# c3-card.net
KiCad netlist of a schematic drawn in EAGLE
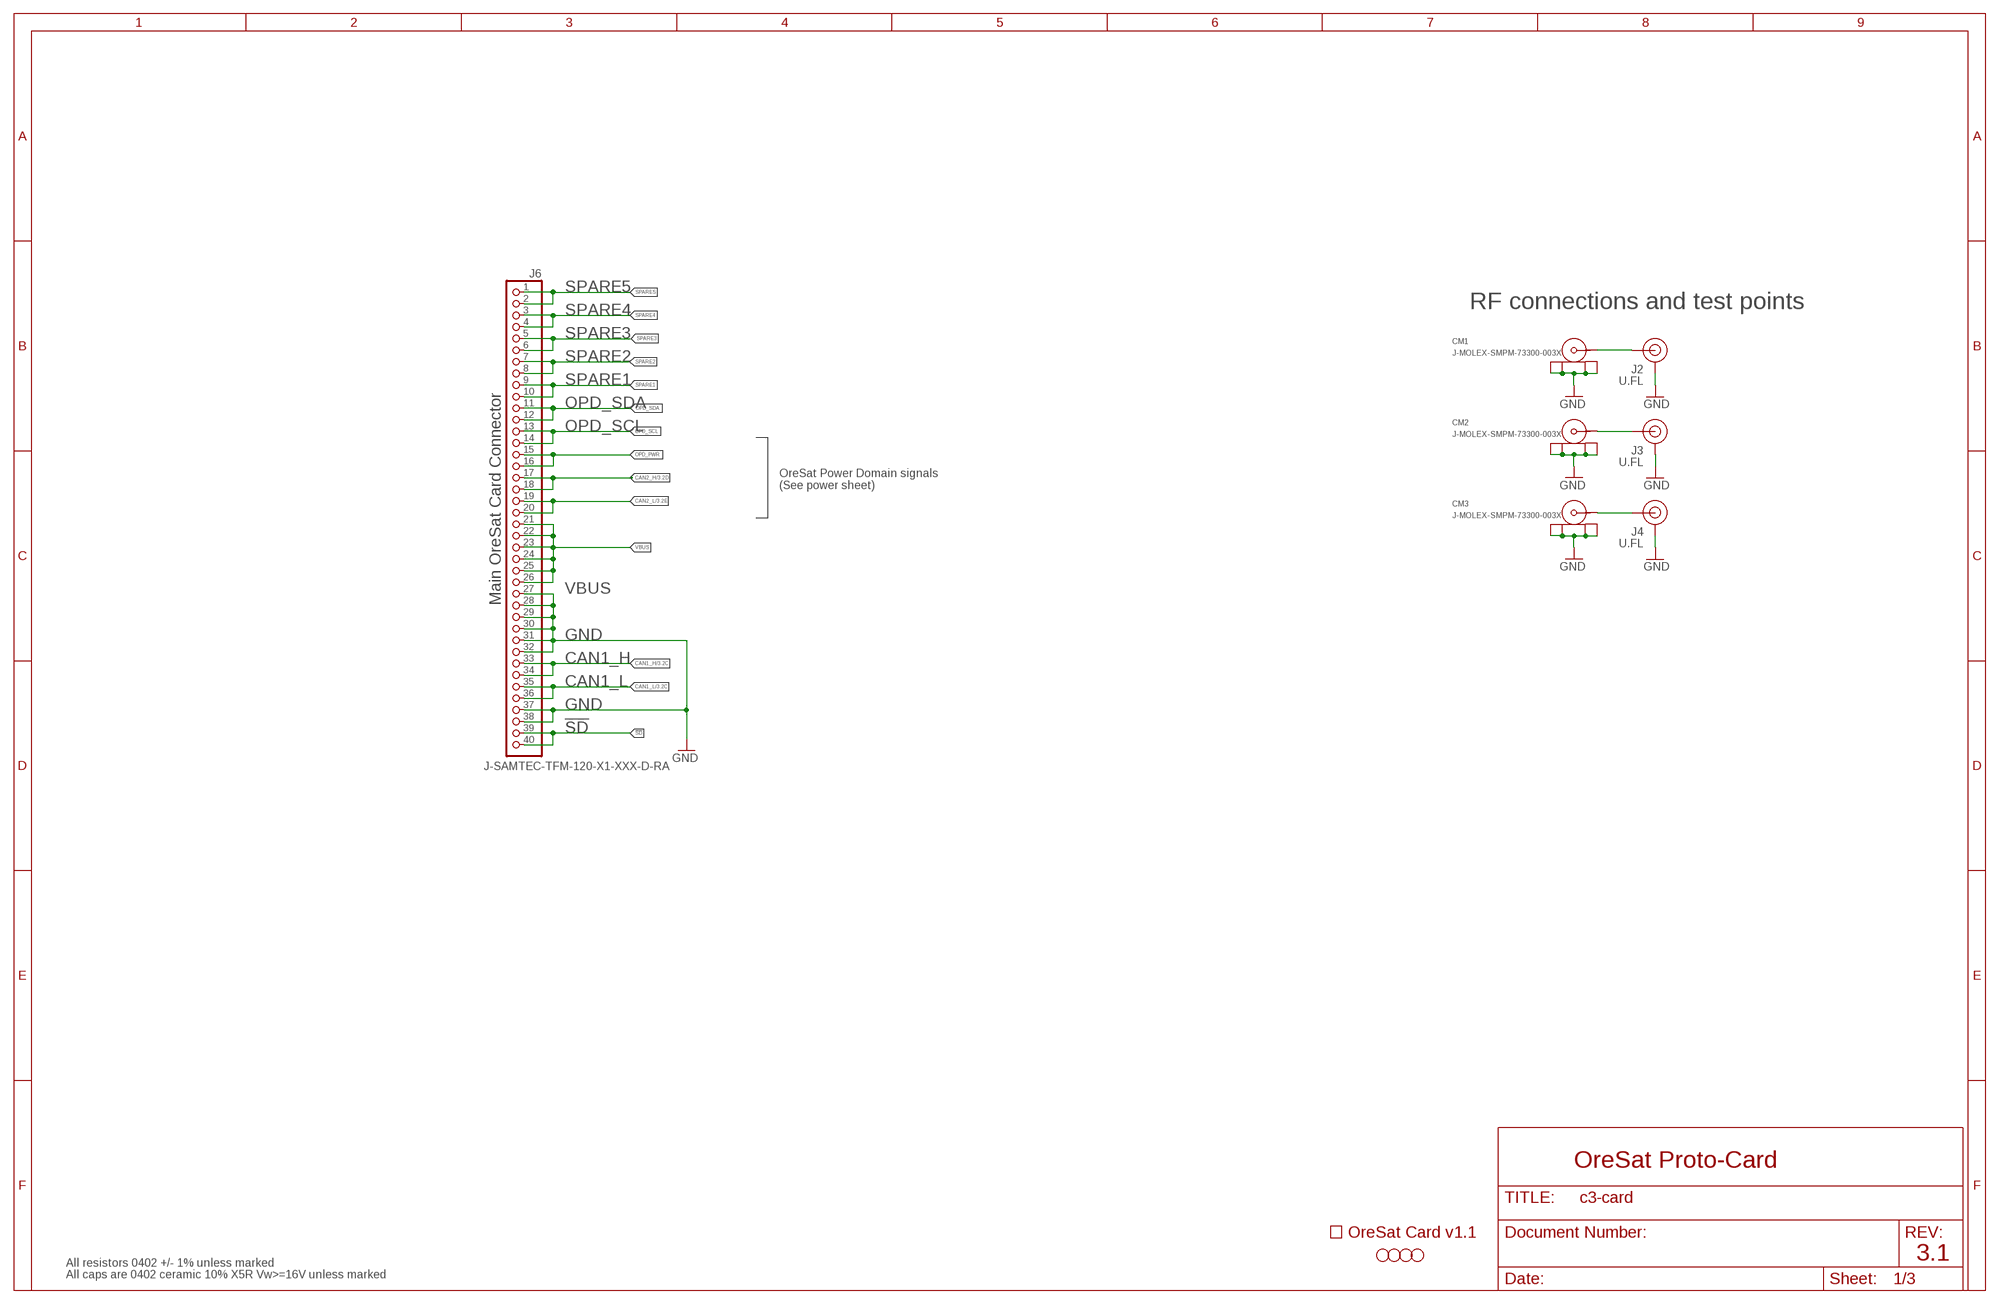
[diagram p0: schematic, sheet 1]
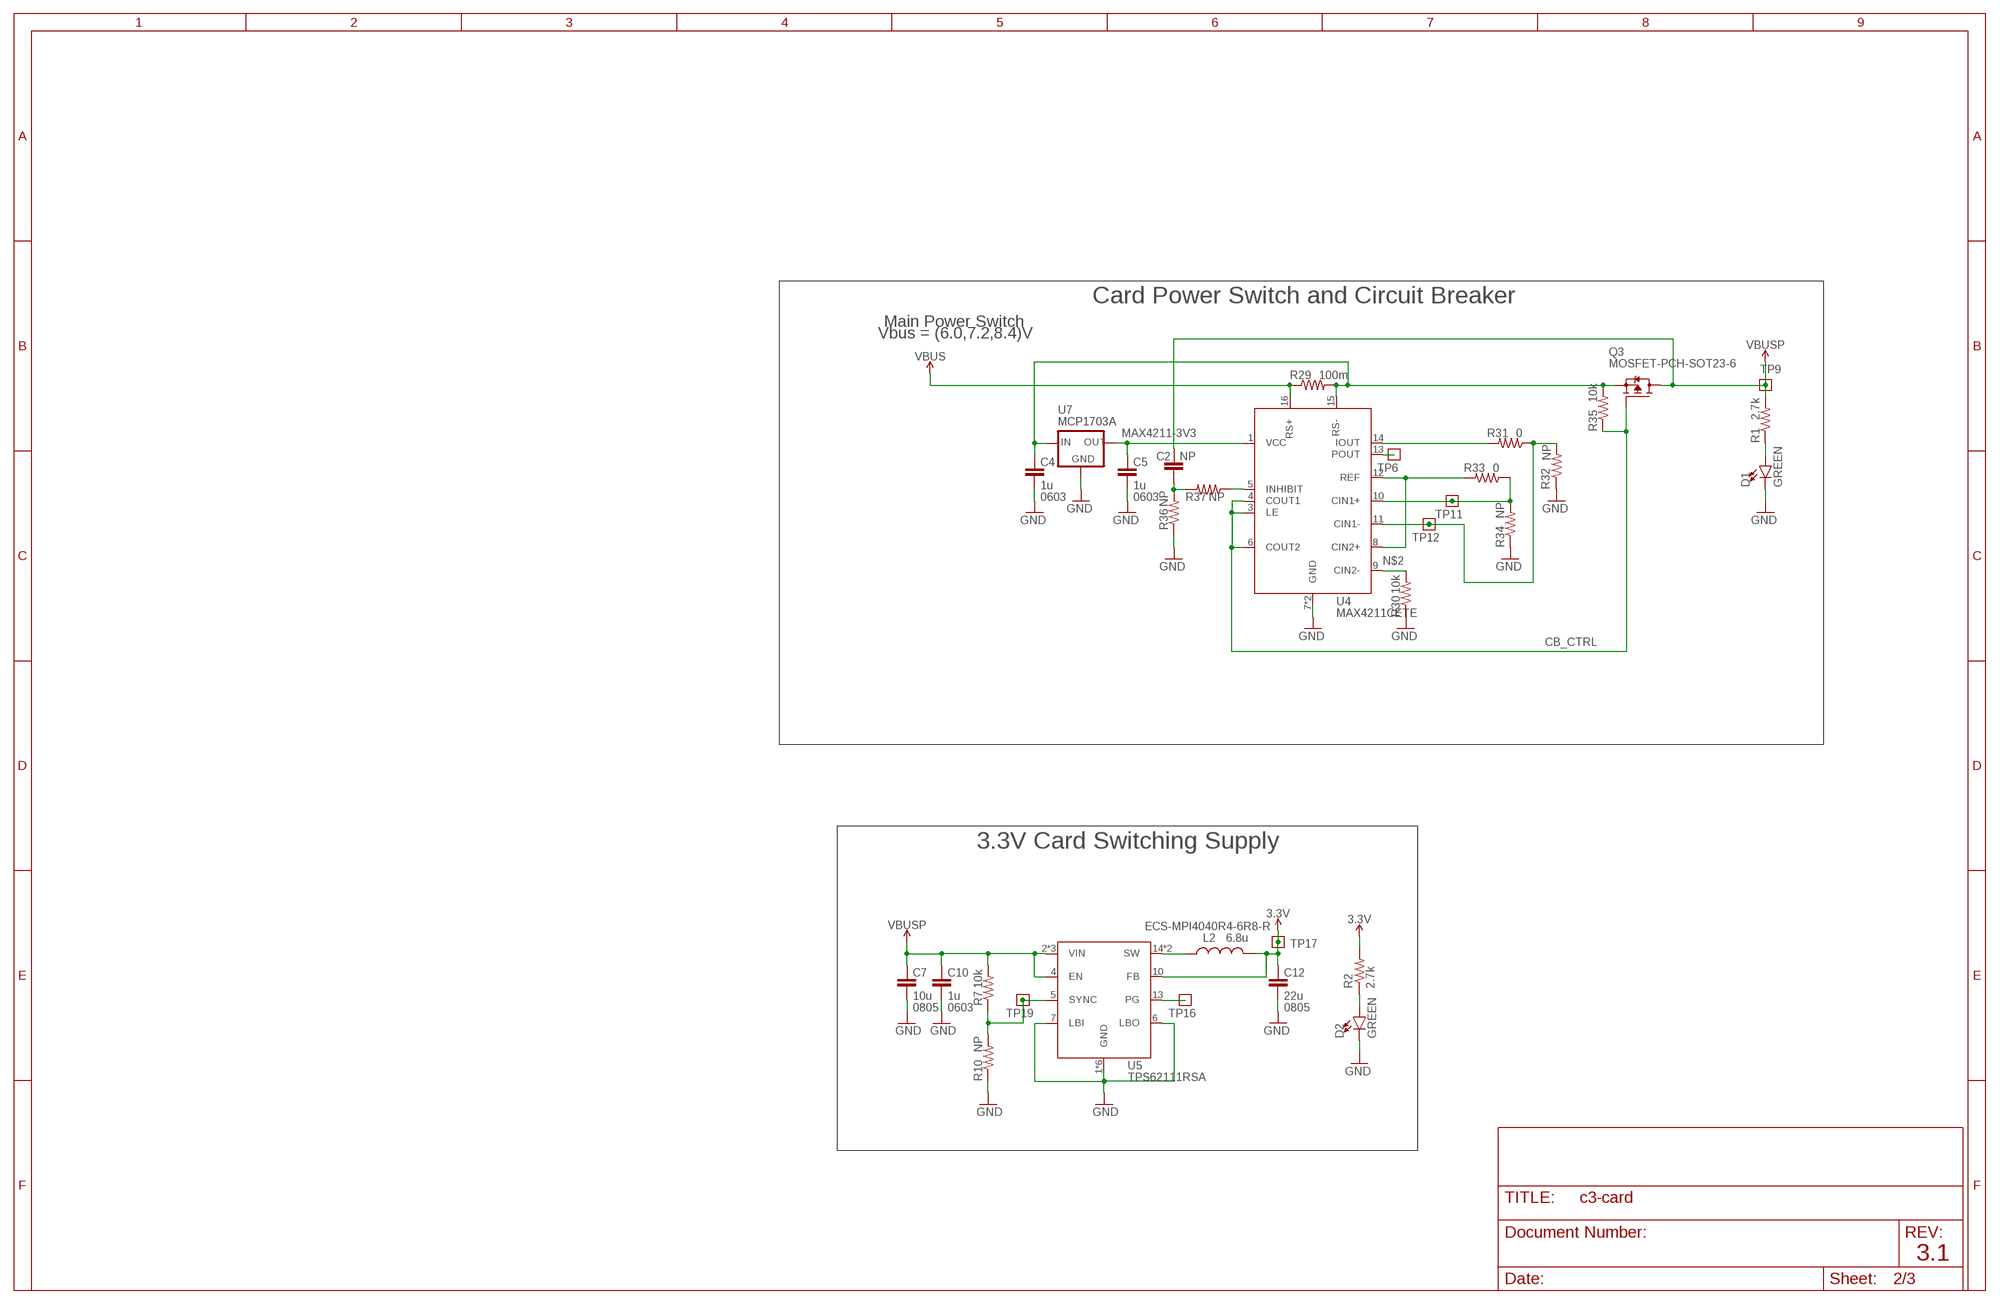
[diagram p1: schematic, sheet 2]
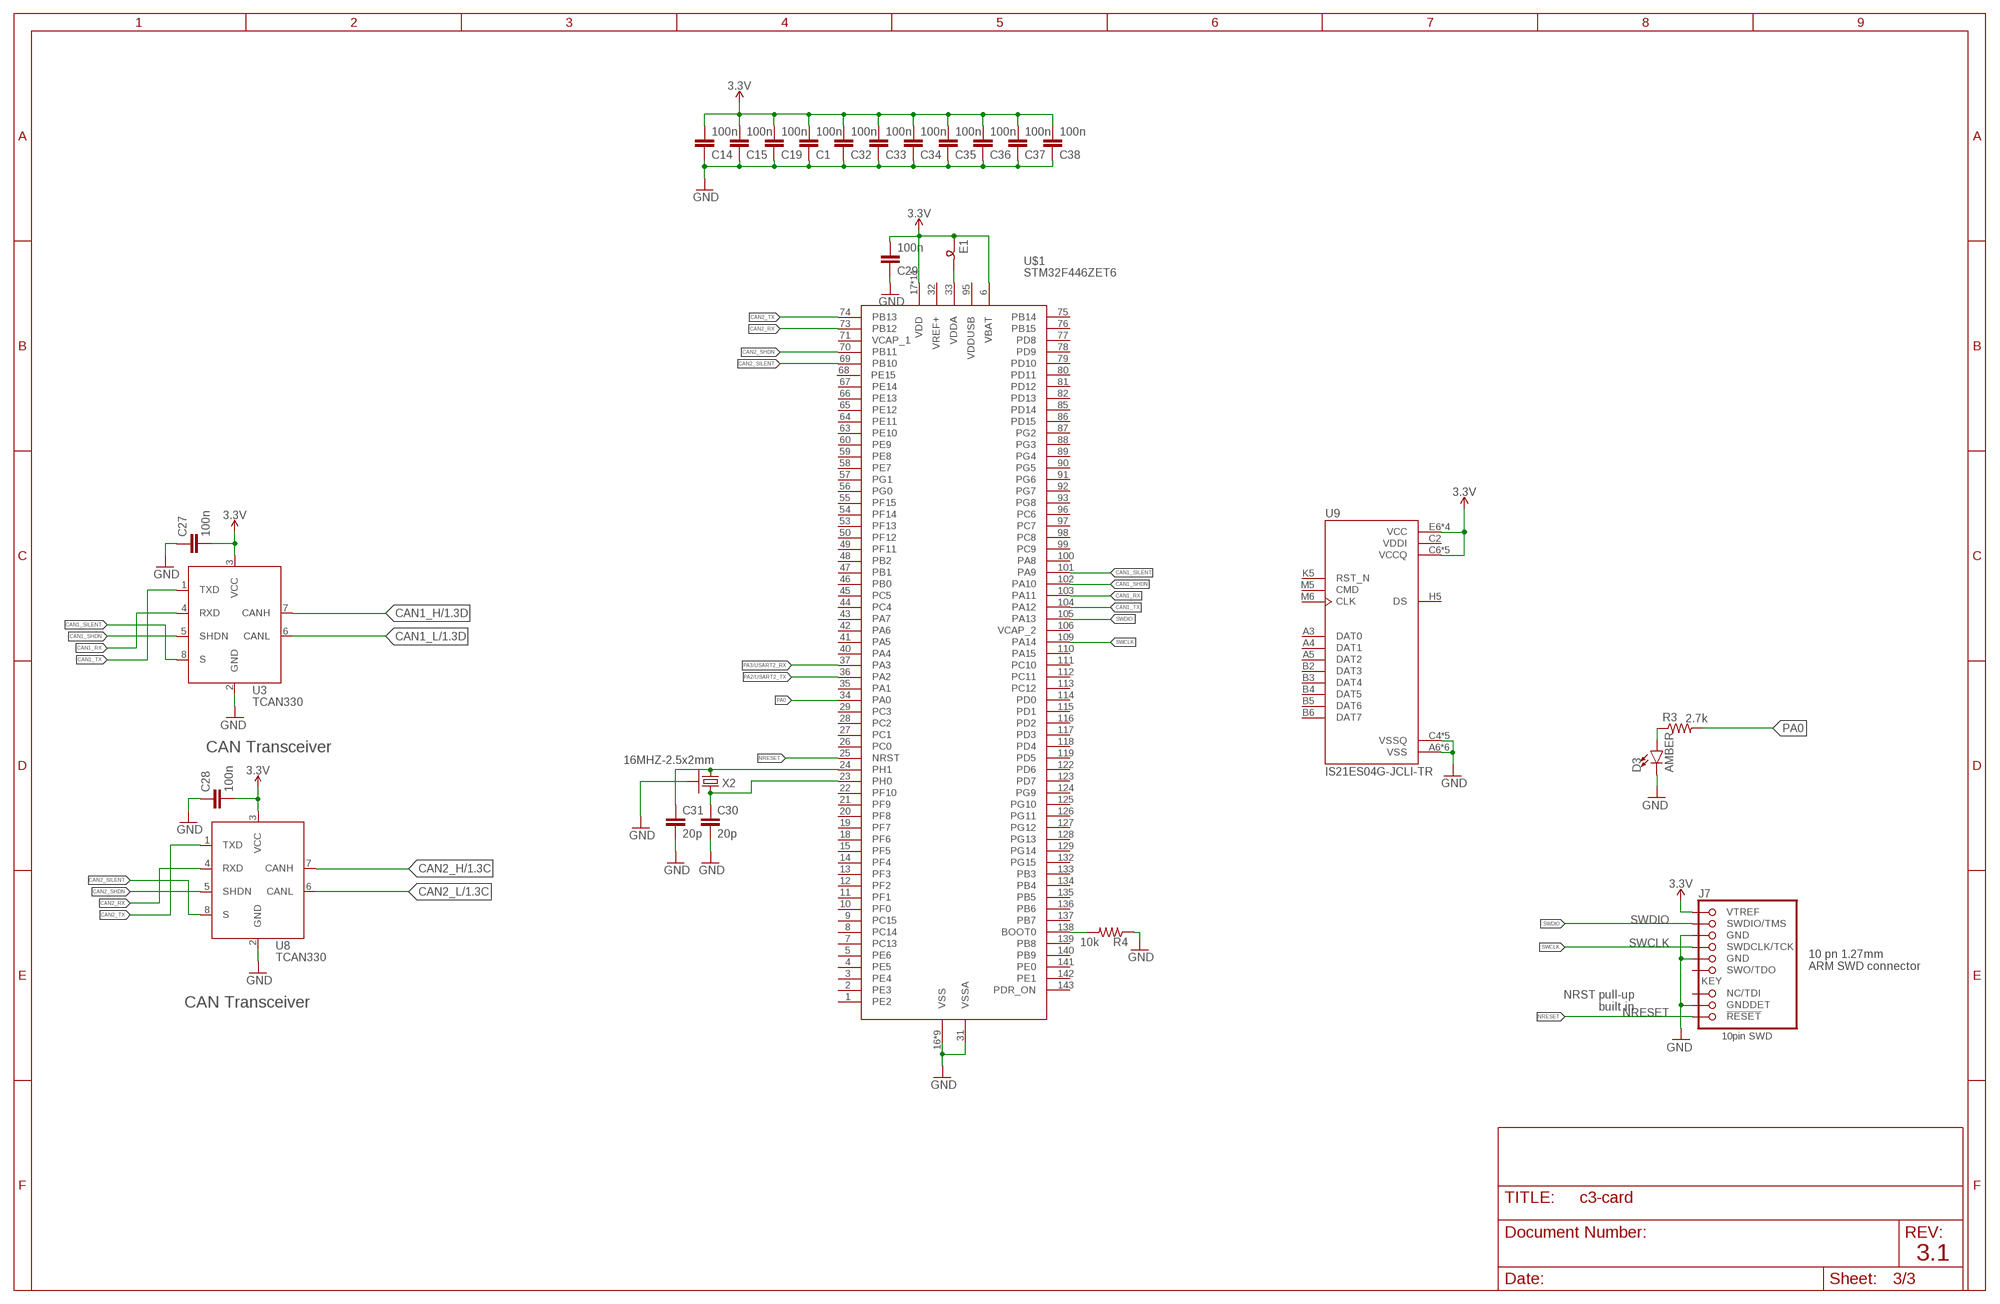
[diagram p2: schematic, sheet 3]

(export (version "E")
  (design (tool "Eeschema 10.0.6"))
  (components
    (comp (ref "C2")
      (value "NP")
      (footprint "eagle-import:.0402-B-NOSILK")
      (fields (field (name "MFR") "Samsung") (field (name "MPN") "CL05B104KO5NNNC"))
      (libsource (lib "eagle-import") (part "rcl_custom_C-EU0402-B-NOSILK"))
    )
    (comp (ref "C4")
      (value "1u")
      (footprint "eagle-import:.0603-B-NOSILK")
      (fields (field (name "MFR") "Samsung") (field (name "MPN") "CL05B104KO5NNNC"))
      (libsource (lib "eagle-import") (part "C-EU0603-B-NOSILK"))
    )
    (comp (ref "C5")
      (value "1u")
      (footprint "eagle-import:.0603-B-NOSILK")
      (fields (field (name "MFR") "Samsung") (field (name "MPN") "CL05B104KO5NNNC"))
      (libsource (lib "eagle-import") (part "C-EU0603-B-NOSILK"))
    )
    (comp (ref "C7")
      (value "10u")
      (footprint "eagle-import:.0805-B-NOSILK")
      (libsource (lib "eagle-import") (part "C-EU0805-B-NOSILK"))
    )
    (comp (ref "C10")
      (value "1u")
      (footprint "eagle-import:.0603-B-NOSILK")
      (fields (field (name "MFR") "Samsung") (field (name "MPN") "CL05B104KO5NNNC"))
      (libsource (lib "eagle-import") (part "C-EU0603-B-NOSILK"))
    )
    (comp (ref "C12")
      (value "22u")
      (footprint "eagle-import:.0805-B-NOSILK")
      (libsource (lib "eagle-import") (part "C-EU0805-B-NOSILK"))
    )
    (comp (ref "D1")
      (value "GREEN")
      (footprint "eagle-import:LED-0603")
      (libsource (lib "eagle-import") (part "LED-GREEN0603"))
    )
    (comp (ref "D2")
      (value "GREEN")
      (footprint "eagle-import:LED-0603")
      (libsource (lib "eagle-import") (part "LED-GREEN0603"))
    )
    (comp (ref "L2")
      (value "6.8u")
      (footprint "eagle-import:ECS-MPI4040")
      (fields (field (name "MFR") "ECS") (field (name "MPN") "ECS-MPI4040R4-6R8-R"))
      (libsource (lib "eagle-import") (part "L-ECS-MPI4040"))
    )
    (comp (ref "Q3")
      (value "MOSFET-PCH-SOT23-6")
      (footprint "eagle-import:SOT23-6")
      (fields (field (name "MFR") "Diodes Inc") (field (name "MPN") "DMP3050LVT-7"))
      (libsource (lib "eagle-import") (part "MOSFET-PCH-SOT23-6"))
    )
    (comp (ref "R1")
      (value "2.7k")
      (footprint "eagle-import:.0402-B-NOSILK")
      (fields (field (name "MFR") "Samsung") (field (name "MPN") "RC1005F6653CS"))
      (libsource (lib "eagle-import") (part "R-US_0402-B-NOSILK"))
    )
    (comp (ref "R2")
      (value "2.7k")
      (footprint "eagle-import:.0402-B-NOSILK")
      (fields (field (name "MFR") "Samsung") (field (name "MPN") "RC1005F6653CS"))
      (libsource (lib "eagle-import") (part "R-US_0402-B-NOSILK"))
    )
    (comp (ref "R7")
      (value "10k")
      (footprint "eagle-import:.0402-B-NOSILK")
      (fields (field (name "MFR") "Samsung") (field (name "MPN") "RC1005F6653CS"))
      (libsource (lib "eagle-import") (part "R-US_0402-B-NOSILK"))
    )
    (comp (ref "R10")
      (value "NP")
      (footprint "eagle-import:.0402-B-NOSILK")
      (fields (field (name "MFR") "Samsung") (field (name "MPN") "RC1005F6653CS"))
      (libsource (lib "eagle-import") (part "R-US_0402-B-NOSILK"))
    )
    (comp (ref "R29")
      (value "100m")
      (footprint "eagle-import:R1206")
      (libsource (lib "eagle-import") (part "R-US_R1206"))
    )
    (comp (ref "R30")
      (value "10k")
      (footprint "eagle-import:.0402-B-NOSILK")
      (fields (field (name "MFR") "Samsung") (field (name "MPN") "RC1005F6653CS"))
      (libsource (lib "eagle-import") (part "R-US_0402-B-NOSILK"))
    )
    (comp (ref "R31")
      (value "0")
      (footprint "eagle-import:.0402-B-NOSILK")
      (fields (field (name "MFR") "Samsung") (field (name "MPN") "RC1005F6653CS"))
      (libsource (lib "eagle-import") (part "R-US_0402-B-NOSILK"))
    )
    (comp (ref "R32")
      (value "NP")
      (footprint "eagle-import:.0402-B-NOSILK")
      (fields (field (name "MFR") "Samsung") (field (name "MPN") "RC1005F6653CS"))
      (libsource (lib "eagle-import") (part "R-US_0402-B-NOSILK"))
    )
    (comp (ref "R33")
      (value "0")
      (footprint "eagle-import:.0402-B-NOSILK")
      (fields (field (name "MFR") "Samsung") (field (name "MPN") "RC1005F6653CS"))
      (libsource (lib "eagle-import") (part "R-US_0402-B-NOSILK"))
    )
    (comp (ref "R34")
      (value "NP")
      (footprint "eagle-import:.0402-B-NOSILK")
      (fields (field (name "MFR") "Samsung") (field (name "MPN") "RC1005F6653CS"))
      (libsource (lib "eagle-import") (part "R-US_0402-B-NOSILK"))
    )
    (comp (ref "R35")
      (value "10k")
      (footprint "eagle-import:.0402-B-NOSILK")
      (fields (field (name "MFR") "Samsung") (field (name "MPN") "RC1005F6653CS"))
      (libsource (lib "eagle-import") (part "R-US_0402-B-NOSILK"))
    )
    (comp (ref "R36")
      (value "NP")
      (footprint "eagle-import:.0402-B-NOSILK")
      (fields (field (name "MFR") "Samsung") (field (name "MPN") "RC1005F6653CS"))
      (libsource (lib "eagle-import") (part "R-US_0402-B-NOSILK"))
    )
    (comp (ref "R37")
      (value "NP")
      (footprint "eagle-import:.0402-B-NOSILK")
      (fields (field (name "MFR") "Samsung") (field (name "MPN") "RC1005F6653CS"))
      (libsource (lib "eagle-import") (part "R-US_0402-B-NOSILK"))
    )
    (comp (ref "TP6")
      (value "TEST-POINT")
      (footprint "eagle-import:2MM-TEST-POINT")
      (libsource (lib "eagle-import") (part "TEST-POINT"))
    )
    (comp (ref "TP9")
      (value "TEST-POINT")
      (footprint "eagle-import:2MM-TEST-POINT")
      (libsource (lib "eagle-import") (part "TEST-POINT"))
    )
    (comp (ref "TP11")
      (value "TEST-POINT")
      (footprint "eagle-import:2MM-TEST-POINT")
      (libsource (lib "eagle-import") (part "TEST-POINT"))
    )
    (comp (ref "TP12")
      (value "TEST-POINT")
      (footprint "eagle-import:2MM-TEST-POINT")
      (libsource (lib "eagle-import") (part "TEST-POINT"))
    )
    (comp (ref "TP16")
      (value "TEST-POINT")
      (footprint "eagle-import:2MM-TEST-POINT")
      (libsource (lib "eagle-import") (part "TEST-POINT"))
    )
    (comp (ref "TP17")
      (value "TEST-POINT")
      (footprint "eagle-import:2MM-TEST-POINT")
      (libsource (lib "eagle-import") (part "TEST-POINT"))
    )
    (comp (ref "TP19")
      (value "TEST-POINT")
      (footprint "eagle-import:2MM-TEST-POINT")
      (libsource (lib "eagle-import") (part "TEST-POINT"))
    )
    (comp (ref "U4")
      (value "MAX4211CETE")
      (footprint "eagle-import:QFN65P400X400X80-17T210")
      (fields (field (name "MFR") "Maxim"))
      (libsource (lib "eagle-import") (part "MAX4211"))
    )
    (comp (ref "U5")
      (value "TPS62111RSA")
      (footprint "eagle-import:S-PVQFN-16")
      (fields (field (name "MFR") "TI"))
      (libsource (lib "eagle-import") (part "TPS6211X"))
    )
    (comp (ref "U7")
      (value "MCP1703A")
      (footprint "eagle-import:SOT23")
      (fields (field (name "MFR") "Microchip") (field (name "MPN") "MCP1703AT-3302E/CB"))
      (libsource (lib "eagle-import") (part "XC63FPM"))
    )
    (comp (ref "C1")
      (value "100n")
      (footprint "eagle-import:.0402-B-NOSILK")
      (fields (field (name "MFR") "Samsung") (field (name "MPN") "CL05B104KO5NNNC"))
      (libsource (lib "eagle-import") (part "rcl_custom_C-EU0402-B-NOSILK"))
    )
    (comp (ref "C14")
      (value "100n")
      (footprint "eagle-import:.0402-B-NOSILK")
      (fields (field (name "MFR") "Samsung") (field (name "MPN") "CL05B104KO5NNNC"))
      (libsource (lib "eagle-import") (part "rcl_custom_C-EU0402-B-NOSILK"))
    )
    (comp (ref "C15")
      (value "100n")
      (footprint "eagle-import:.0402-B-NOSILK")
      (fields (field (name "MFR") "Samsung") (field (name "MPN") "CL05B104KO5NNNC"))
      (libsource (lib "eagle-import") (part "rcl_custom_C-EU0402-B-NOSILK"))
    )
    (comp (ref "C19")
      (value "100n")
      (footprint "eagle-import:.0402-B-NOSILK")
      (fields (field (name "MFR") "Samsung") (field (name "MPN") "CL05B104KO5NNNC"))
      (libsource (lib "eagle-import") (part "rcl_custom_C-EU0402-B-NOSILK"))
    )
    (comp (ref "C27")
      (value "100n")
      (footprint "eagle-import:.0402-B-NOSILK")
      (fields (field (name "MFR") "Samsung") (field (name "MPN") "CL05B104KO5NNNC"))
      (libsource (lib "eagle-import") (part "rcl_custom_C-EU0402-B-NOSILK"))
    )
    (comp (ref "C28")
      (value "100n")
      (footprint "eagle-import:.0402-B-NOSILK")
      (fields (field (name "MFR") "Samsung") (field (name "MPN") "CL05B104KO5NNNC"))
      (libsource (lib "eagle-import") (part "rcl_custom_C-EU0402-B-NOSILK"))
    )
    (comp (ref "C29")
      (value "100n")
      (footprint "eagle-import:.0402-B-NOSILK")
      (fields (field (name "MFR") "Samsung") (field (name "MPN") "CL05B104KO5NNNC"))
      (libsource (lib "eagle-import") (part "rcl_custom_C-EU0402-B-NOSILK"))
    )
    (comp (ref "C30")
      (value "20p")
      (footprint "eagle-import:.0402-B-NOSILK")
      (fields (field (name "MFR") "Samsung") (field (name "MPN") "CL05C200JB51PNC"))
      (libsource (lib "eagle-import") (part "rcl_custom_C-EU0402-B-NOSILK"))
    )
    (comp (ref "C31")
      (value "20p")
      (footprint "eagle-import:.0402-B-NOSILK")
      (fields (field (name "MFR") "Samsung") (field (name "MPN") "CL05C200JB51PNC"))
      (libsource (lib "eagle-import") (part "rcl_custom_C-EU0402-B-NOSILK"))
    )
    (comp (ref "C32")
      (value "100n")
      (footprint "eagle-import:.0402-B-NOSILK")
      (fields (field (name "MFR") "Samsung") (field (name "MPN") "CL05B104KO5NNNC"))
      (libsource (lib "eagle-import") (part "rcl_custom_C-EU0402-B-NOSILK"))
    )
    (comp (ref "C33")
      (value "100n")
      (footprint "eagle-import:.0402-B-NOSILK")
      (fields (field (name "MFR") "Samsung") (field (name "MPN") "CL05B104KO5NNNC"))
      (libsource (lib "eagle-import") (part "rcl_custom_C-EU0402-B-NOSILK"))
    )
    (comp (ref "C34")
      (value "100n")
      (footprint "eagle-import:.0402-B-NOSILK")
      (fields (field (name "MFR") "Samsung") (field (name "MPN") "CL05B104KO5NNNC"))
      (libsource (lib "eagle-import") (part "rcl_custom_C-EU0402-B-NOSILK"))
    )
    (comp (ref "C35")
      (value "100n")
      (footprint "eagle-import:.0402-B-NOSILK")
      (fields (field (name "MFR") "Samsung") (field (name "MPN") "CL05B104KO5NNNC"))
      (libsource (lib "eagle-import") (part "rcl_custom_C-EU0402-B-NOSILK"))
    )
    (comp (ref "C36")
      (value "100n")
      (footprint "eagle-import:.0402-B-NOSILK")
      (fields (field (name "MFR") "Samsung") (field (name "MPN") "CL05B104KO5NNNC"))
      (libsource (lib "eagle-import") (part "rcl_custom_C-EU0402-B-NOSILK"))
    )
    (comp (ref "C37")
      (value "100n")
      (footprint "eagle-import:.0402-B-NOSILK")
      (fields (field (name "MFR") "Samsung") (field (name "MPN") "CL05B104KO5NNNC"))
      (libsource (lib "eagle-import") (part "rcl_custom_C-EU0402-B-NOSILK"))
    )
    (comp (ref "C38")
      (value "100n")
      (footprint "eagle-import:.0402-B-NOSILK")
      (fields (field (name "MFR") "Samsung") (field (name "MPN") "CL05B104KO5NNNC"))
      (libsource (lib "eagle-import") (part "rcl_custom_C-EU0402-B-NOSILK"))
    )
    (comp (ref "D3")
      (value "AMBER")
      (footprint "eagle-import:LED-0603")
      (libsource (lib "eagle-import") (part "LED-GREEN0603"))
    )
    (comp (ref "E1")
      (value "L-BEAD-0603-B")
      (footprint "eagle-import:.0603-B")
      (libsource (lib "eagle-import") (part "L-BEAD-0603-B"))
    )
    (comp (ref "J7")
      (value "FTSH-105-XX-X-DV-K")
      (footprint "eagle-import:CON10_2X5_DUK_FTSH")
      (fields (field (name "MFR") "Samtec") (field (name "MPN") "FTSH-105-01-F-DV-K"))
      (libsource (lib "eagle-import") (part "FTSH-105-XX-X-DV-K"))
    )
    (comp (ref "R3")
      (value "2.7k")
      (footprint "eagle-import:.0402-B-NOSILK")
      (fields (field (name "MFR") "Samsung") (field (name "MPN") "RC1005F6653CS"))
      (libsource (lib "eagle-import") (part "R-US_0402-B-NOSILK"))
    )
    (comp (ref "R4")
      (value "10k")
      (footprint "eagle-import:.0402-B-NOSILK")
      (fields (field (name "MFR") "Samsung") (field (name "MPN") "RC1005F6653CS"))
      (libsource (lib "eagle-import") (part "R-US_0402-B-NOSILK"))
    )
    (comp (ref "U$1")
      (value "STM32F446ZET6")
      (footprint "eagle-import:P-TQFP-144-19")
      (libsource (lib "eagle-import") (part "STM32F446ZET6"))
    )
    (comp (ref "U3")
      (value "TCAN330")
      (footprint "eagle-import:SOT23-8_TI-DCN")
      (fields (field (name "MFR") "Texas Instruments") (field (name "MPN") "TCAN330GDCNT"))
      (libsource (lib "eagle-import") (part "TCAN330"))
    )
    (comp (ref "U8")
      (value "TCAN330")
      (footprint "eagle-import:SOT23-8_TI-DCN")
      (fields (field (name "MFR") "Texas Instruments") (field (name "MPN") "TCAN330GDCNT"))
      (libsource (lib "eagle-import") (part "TCAN330"))
    )
    (comp (ref "U9")
      (value "IS21ES04G-JCLI-TR")
      (footprint "eagle-import:BGA153N50P14X14_1150X1300X100")
      (fields (field (name "MF") "ISSI, Integrated Silicon Solution Inc"))
      (libsource (lib "eagle-import") (part "IS21ES04G-JCLI-TR"))
    )
    (comp (ref "X2")
      (value "16MHZ-2.5x2mm")
      (footprint "eagle-import:CRYSTAL_2.5X2")
      (fields (field (name "MFR") "ECS Inc.") (field (name "MPN") "ECS-160-10-36Q-ES-TR"))
      (libsource (lib "eagle-import") (part "CRYSTAL-WITH-GND"))
    )
    (comp (ref "CM1")
      (value "J-MOLEX-SMPM-73300-003X")
      (footprint "eagle-import:J-MOLEX-SMPM-073300-003X")
      (fields (field (name "MFR") "Molex") (field (name "MPN") "73300-0020"))
      (libsource (lib "eagle-import") (part "J-MOLEX-SMPM-73300-003X"))
    )
    (comp (ref "CM2")
      (value "J-MOLEX-SMPM-73300-003X")
      (footprint "eagle-import:J-MOLEX-SMPM-073300-003X")
      (fields (field (name "MFR") "Molex") (field (name "MPN") "73300-0020"))
      (libsource (lib "eagle-import") (part "J-MOLEX-SMPM-73300-003X"))
    )
    (comp (ref "CM3")
      (value "J-MOLEX-SMPM-73300-003X")
      (footprint "eagle-import:J-MOLEX-SMPM-073300-003X")
      (fields (field (name "MFR") "Molex") (field (name "MPN") "73300-0020"))
      (libsource (lib "eagle-import") (part "J-MOLEX-SMPM-73300-003X"))
    )
    (comp (ref "H1")
      (value "STAND-OFFTIGHT")
      (footprint "eagle-import:STAND-OFF-TIGHT")
      (libsource (lib "eagle-import") (part "STAND-OFFTIGHT"))
    )
    (comp (ref "H2")
      (value "STAND-OFFTIGHT")
      (footprint "eagle-import:STAND-OFF-TIGHT")
      (libsource (lib "eagle-import") (part "STAND-OFFTIGHT"))
    )
    (comp (ref "H3")
      (value "STAND-OFFTIGHT")
      (footprint "eagle-import:STAND-OFF-TIGHT")
      (libsource (lib "eagle-import") (part "STAND-OFFTIGHT"))
    )
    (comp (ref "H4")
      (value "STAND-OFFTIGHT")
      (footprint "eagle-import:STAND-OFF-TIGHT")
      (libsource (lib "eagle-import") (part "STAND-OFFTIGHT"))
    )
    (comp (ref "J2")
      (value "U.FL")
      (footprint "eagle-import:U.FL")
      (libsource (lib "eagle-import") (part "U.FL2PIN"))
    )
    (comp (ref "J3")
      (value "U.FL")
      (footprint "eagle-import:U.FL")
      (libsource (lib "eagle-import") (part "U.FL2PIN"))
    )
    (comp (ref "J4")
      (value "U.FL")
      (footprint "eagle-import:U.FL")
      (libsource (lib "eagle-import") (part "U.FL2PIN"))
    )
    (comp (ref "J6")
      (value "J-SAMTEC-TFM-120-X1-XXX-D-RA")
      (footprint "eagle-import:J-SAMTEC-TFM-120-X1-XXX-D-RA")
      (fields (field (name "MFR") "Samtec") (field (name "MPN") "TFM-120-01-L-D-RA"))
      (libsource (lib "eagle-import") (part "J-SAMTEC-TFM-120-X1-XXX-D-RA"))
    )
    (comp (ref "U$2")
      (value "ORESAT-CARD-V1.1-3XRF")
      (footprint "eagle-import:ORESAT-CARD-V1.1-3XRF")
      (libsource (lib "eagle-import") (part "ORESAT-CARD-V1.1-3XRF"))
    )
  )
  (nets
    (net (code "1") (name "3.3V") (class "Default")
      (node (ref "C1") (pin "2") (pinfunction "2_2") (pintype "passive"))
      (node (ref "C12") (pin "1") (pinfunction "1_1") (pintype "passive"))
      (node (ref "C14") (pin "2") (pinfunction "2_2") (pintype "passive"))
      (node (ref "C15") (pin "2") (pinfunction "2_2") (pintype "passive"))
      (node (ref "C19") (pin "2") (pinfunction "2_2") (pintype "passive"))
      (node (ref "C27") (pin "2") (pinfunction "2_2") (pintype "passive"))
      (node (ref "C28") (pin "2") (pinfunction "2_2") (pintype "passive"))
      (node (ref "C29") (pin "2") (pinfunction "2_2") (pintype "passive"))
      (node (ref "C32") (pin "2") (pinfunction "2_2") (pintype "passive"))
      (node (ref "C33") (pin "2") (pinfunction "2_2") (pintype "passive"))
      (node (ref "C34") (pin "2") (pinfunction "2_2") (pintype "passive"))
      (node (ref "C35") (pin "2") (pinfunction "2_2") (pintype "passive"))
      (node (ref "C36") (pin "2") (pinfunction "2_2") (pintype "passive"))
      (node (ref "C37") (pin "2") (pinfunction "2_2") (pintype "passive"))
      (node (ref "C38") (pin "2") (pinfunction "2_2") (pintype "passive"))
      (node (ref "E1") (pin "1") (pinfunction "1_1") (pintype "passive"))
      (node (ref "J7") (pin "1") (pinfunction "VTREF_1") (pintype "passive"))
      (node (ref "L2") (pin "2") (pinfunction "2_2") (pintype "passive"))
      (node (ref "R2") (pin "2") (pinfunction "2_2") (pintype "passive"))
      (node (ref "TP17") (pin "1") (pinfunction "1_1") (pintype "passive"))
      (node (ref "U$1") (pin "108") (pinfunction "VDD_108") (pintype "bidirectional"))
      (node (ref "U$1") (pin "121") (pinfunction "VDD_121") (pintype "bidirectional"))
      (node (ref "U$1") (pin "131") (pinfunction "VDD_131") (pintype "bidirectional"))
      (node (ref "U$1") (pin "144") (pinfunction "VDD_144") (pintype "bidirectional"))
      (node (ref "U$1") (pin "17") (pinfunction "VDD_17") (pintype "bidirectional"))
      (node (ref "U$1") (pin "30") (pinfunction "VDD_30") (pintype "bidirectional"))
      (node (ref "U$1") (pin "39") (pinfunction "VDD_39") (pintype "bidirectional"))
      (node (ref "U$1") (pin "52") (pinfunction "VDD_52") (pintype "bidirectional"))
      (node (ref "U$1") (pin "6") (pinfunction "VBAT_6") (pintype "bidirectional"))
      (node (ref "U$1") (pin "62") (pinfunction "VDD_62") (pintype "bidirectional"))
      (node (ref "U$1") (pin "72") (pinfunction "VDD_72") (pintype "bidirectional"))
      (node (ref "U$1") (pin "84") (pinfunction "VDD_84") (pintype "bidirectional"))
      (node (ref "U3") (pin "3") (pinfunction "VCC_3") (pintype "power_in"))
      (node (ref "U5") (pin "10") (pinfunction "FB_10") (pintype "input"))
      (node (ref "U8") (pin "3") (pinfunction "VCC_3") (pintype "power_in"))
      (node (ref "U9") (pin "C6") (pinfunction "VCCQ_C6") (pintype "power_in"))
      (node (ref "U9") (pin "E6") (pinfunction "VCC_E6") (pintype "power_in"))
      (node (ref "U9") (pin "F5") (pinfunction "VCC_F5") (pintype "power_in"))
      (node (ref "U9") (pin "J10") (pinfunction "VCC_J10") (pintype "power_in"))
      (node (ref "U9") (pin "K9") (pinfunction "VCC_K9") (pintype "power_in"))
      (node (ref "U9") (pin "M4") (pinfunction "VCCQ_M4") (pintype "power_in"))
      (node (ref "U9") (pin "N4") (pinfunction "VCCQ_N4") (pintype "power_in"))
      (node (ref "U9") (pin "P3") (pinfunction "VCCQ_P3") (pintype "power_in"))
      (node (ref "U9") (pin "P5") (pinfunction "VCCQ_P5") (pintype "power_in"))
    )
    (net (code "2") (name "CAN1_H") (class "Default")
      (node (ref "J6") (pin "33") (pinfunction "33_33") (pintype "passive"))
      (node (ref "J6") (pin "34") (pinfunction "34_34") (pintype "passive"))
      (node (ref "U3") (pin "7") (pinfunction "CANH_7") (pintype "bidirectional"))
    )
    (net (code "3") (name "CAN1_L") (class "Default")
      (node (ref "J6") (pin "35") (pinfunction "35_35") (pintype "passive"))
      (node (ref "J6") (pin "36") (pinfunction "36_36") (pintype "passive"))
      (node (ref "U3") (pin "6") (pinfunction "CANL_6") (pintype "bidirectional"))
    )
    (net (code "4") (name "CAN1_RX") (class "Default")
      (node (ref "U$1") (pin "103") (pinfunction "PA11_103") (pintype "bidirectional"))
      (node (ref "U3") (pin "4") (pinfunction "RXD_4") (pintype "output"))
    )
    (net (code "5") (name "CAN1_SHDN") (class "Default")
      (node (ref "U$1") (pin "102") (pinfunction "PA10_102") (pintype "bidirectional"))
      (node (ref "U3") (pin "5") (pinfunction "SHDN_5") (pintype "input"))
    )
    (net (code "6") (name "CAN1_SILENT") (class "Default")
      (node (ref "U$1") (pin "101") (pinfunction "PA9_101") (pintype "bidirectional"))
      (node (ref "U3") (pin "8") (pinfunction "S_8") (pintype "input"))
    )
    (net (code "7") (name "CAN1_TX") (class "Default")
      (node (ref "U$1") (pin "104") (pinfunction "PA12_104") (pintype "bidirectional"))
      (node (ref "U3") (pin "1") (pinfunction "TXD_1") (pintype "input"))
    )
    (net (code "8") (name "CAN2_H") (class "Default")
      (node (ref "J6") (pin "17") (pinfunction "17_17") (pintype "passive"))
      (node (ref "J6") (pin "18") (pinfunction "18_18") (pintype "passive"))
      (node (ref "U8") (pin "7") (pinfunction "CANH_7") (pintype "bidirectional"))
    )
    (net (code "9") (name "CAN2_L") (class "Default")
      (node (ref "J6") (pin "19") (pinfunction "19_19") (pintype "passive"))
      (node (ref "J6") (pin "20") (pinfunction "20_20") (pintype "passive"))
      (node (ref "U8") (pin "6") (pinfunction "CANL_6") (pintype "bidirectional"))
    )
    (net (code "10") (name "CAN2_RX") (class "Default")
      (node (ref "U$1") (pin "73") (pinfunction "PB12_73") (pintype "bidirectional"))
      (node (ref "U8") (pin "4") (pinfunction "RXD_4") (pintype "output"))
    )
    (net (code "11") (name "CAN2_SHDN") (class "Default")
      (node (ref "U$1") (pin "70") (pinfunction "PB11_70") (pintype "bidirectional"))
      (node (ref "U8") (pin "5") (pinfunction "SHDN_5") (pintype "input"))
    )
    (net (code "12") (name "CAN2_SILENT") (class "Default")
      (node (ref "U$1") (pin "69") (pinfunction "PB10_69") (pintype "bidirectional"))
      (node (ref "U8") (pin "8") (pinfunction "S_8") (pintype "input"))
    )
    (net (code "13") (name "CAN2_TX") (class "Default")
      (node (ref "U$1") (pin "74") (pinfunction "PB13_74") (pintype "bidirectional"))
      (node (ref "U8") (pin "1") (pinfunction "TXD_1") (pintype "input"))
    )
    (net (code "14") (name "CB_CTRL") (class "Default")
      (node (ref "Q3") (pin "3") (pinfunction "G_3") (pintype "passive"))
      (node (ref "R35") (pin "1") (pinfunction "1_1") (pintype "passive"))
      (node (ref "U4") (pin "3") (pinfunction "LE_3") (pintype "input"))
      (node (ref "U4") (pin "4") (pinfunction "COUT1_4") (pintype "open_collector"))
      (node (ref "U4") (pin "6") (pinfunction "COUT2_6") (pintype "open_collector"))
    )
    (net (code "15") (name "GND") (class "Default")
      (node (ref "C1") (pin "1") (pinfunction "1_1") (pintype "passive"))
      (node (ref "C10") (pin "2") (pinfunction "2_2") (pintype "passive"))
      (node (ref "C12") (pin "2") (pinfunction "2_2") (pintype "passive"))
      (node (ref "C14") (pin "1") (pinfunction "1_1") (pintype "passive"))
      (node (ref "C15") (pin "1") (pinfunction "1_1") (pintype "passive"))
      (node (ref "C19") (pin "1") (pinfunction "1_1") (pintype "passive"))
      (node (ref "C27") (pin "1") (pinfunction "1_1") (pintype "passive"))
      (node (ref "C28") (pin "1") (pinfunction "1_1") (pintype "passive"))
      (node (ref "C29") (pin "1") (pinfunction "1_1") (pintype "passive"))
      (node (ref "C30") (pin "2") (pinfunction "2_2") (pintype "passive"))
      (node (ref "C31") (pin "2") (pinfunction "2_2") (pintype "passive"))
      (node (ref "C32") (pin "1") (pinfunction "1_1") (pintype "passive"))
      (node (ref "C33") (pin "1") (pinfunction "1_1") (pintype "passive"))
      (node (ref "C34") (pin "1") (pinfunction "1_1") (pintype "passive"))
      (node (ref "C35") (pin "1") (pinfunction "1_1") (pintype "passive"))
      (node (ref "C36") (pin "1") (pinfunction "1_1") (pintype "passive"))
      (node (ref "C37") (pin "1") (pinfunction "1_1") (pintype "passive"))
      (node (ref "C38") (pin "1") (pinfunction "1_1") (pintype "passive"))
      (node (ref "C4") (pin "2") (pinfunction "2_2") (pintype "passive"))
      (node (ref "C5") (pin "2") (pinfunction "2_2") (pintype "passive"))
      (node (ref "C7") (pin "2") (pinfunction "2_2") (pintype "passive"))
      (node (ref "CM1") (pin "P$1") (pinfunction "SHIELD3_P$1") (pintype "passive"))
      (node (ref "CM1") (pin "P$2") (pinfunction "SHIELD2_P$2") (pintype "passive"))
      (node (ref "CM1") (pin "P$3") (pinfunction "SHIELD1_P$3") (pintype "passive"))
      (node (ref "CM1") (pin "P$4") (pinfunction "SHIELD_P$4") (pintype "passive"))
      (node (ref "CM2") (pin "P$1") (pinfunction "SHIELD3_P$1") (pintype "passive"))
      (node (ref "CM2") (pin "P$2") (pinfunction "SHIELD2_P$2") (pintype "passive"))
      (node (ref "CM2") (pin "P$3") (pinfunction "SHIELD1_P$3") (pintype "passive"))
      (node (ref "CM2") (pin "P$4") (pinfunction "SHIELD_P$4") (pintype "passive"))
      (node (ref "CM3") (pin "P$1") (pinfunction "SHIELD3_P$1") (pintype "passive"))
      (node (ref "CM3") (pin "P$2") (pinfunction "SHIELD2_P$2") (pintype "passive"))
      (node (ref "CM3") (pin "P$3") (pinfunction "SHIELD1_P$3") (pintype "passive"))
      (node (ref "CM3") (pin "P$4") (pinfunction "SHIELD_P$4") (pintype "passive"))
      (node (ref "D1") (pin "C") (pinfunction "C_C") (pintype "passive"))
      (node (ref "D2") (pin "C") (pinfunction "C_C") (pintype "passive"))
      (node (ref "D3") (pin "C") (pinfunction "C_C") (pintype "passive"))
      (node (ref "J2") (pin "1") (pinfunction "GND_1") (pintype "bidirectional"))
      (node (ref "J2") (pin "2") (pinfunction "GND_2") (pintype "bidirectional"))
      (node (ref "J3") (pin "1") (pinfunction "GND_1") (pintype "bidirectional"))
      (node (ref "J3") (pin "2") (pinfunction "GND_2") (pintype "bidirectional"))
      (node (ref "J4") (pin "1") (pinfunction "GND_1") (pintype "bidirectional"))
      (node (ref "J4") (pin "2") (pinfunction "GND_2") (pintype "bidirectional"))
      (node (ref "J6") (pin "27") (pinfunction "27_27") (pintype "passive"))
      (node (ref "J6") (pin "28") (pinfunction "28_28") (pintype "passive"))
      (node (ref "J6") (pin "29") (pinfunction "29_29") (pintype "passive"))
      (node (ref "J6") (pin "30") (pinfunction "30_30") (pintype "passive"))
      (node (ref "J6") (pin "31") (pinfunction "31_31") (pintype "passive"))
      (node (ref "J6") (pin "32") (pinfunction "32_32") (pintype "passive"))
      (node (ref "J6") (pin "37") (pinfunction "37_37") (pintype "passive"))
      (node (ref "J6") (pin "38") (pinfunction "38_38") (pintype "passive"))
      (node (ref "J7") (pin "3") (pinfunction "GND_3") (pintype "passive"))
      (node (ref "J7") (pin "5") (pinfunction "GND_5") (pintype "passive"))
      (node (ref "J7") (pin "9") (pinfunction "GNDDET_9") (pintype "passive"))
      (node (ref "R10") (pin "1") (pinfunction "1_1") (pintype "passive"))
      (node (ref "R30") (pin "1") (pinfunction "1_1") (pintype "passive"))
      (node (ref "R32") (pin "1") (pinfunction "1_1") (pintype "passive"))
      (node (ref "R34") (pin "1") (pinfunction "1_1") (pintype "passive"))
      (node (ref "R36") (pin "1") (pinfunction "1_1") (pintype "passive"))
      (node (ref "R4") (pin "1") (pinfunction "1_1") (pintype "passive"))
      (node (ref "U$1") (pin "107") (pinfunction "VSS_107") (pintype "bidirectional"))
      (node (ref "U$1") (pin "120") (pinfunction "VSS_120") (pintype "bidirectional"))
      (node (ref "U$1") (pin "130") (pinfunction "VSS_130") (pintype "bidirectional"))
      (node (ref "U$1") (pin "16") (pinfunction "VSS_16") (pintype "bidirectional"))
      (node (ref "U$1") (pin "31") (pinfunction "VSSA_31") (pintype "bidirectional"))
      (node (ref "U$1") (pin "38") (pinfunction "VSS_38") (pintype "bidirectional"))
      (node (ref "U$1") (pin "51") (pinfunction "VSS_51") (pintype "bidirectional"))
      (node (ref "U$1") (pin "61") (pinfunction "VSS_61") (pintype "bidirectional"))
      (node (ref "U$1") (pin "83") (pinfunction "VSS_83") (pintype "bidirectional"))
      (node (ref "U$1") (pin "94") (pinfunction "VSS_94") (pintype "bidirectional"))
      (node (ref "U3") (pin "2") (pinfunction "GND_2") (pintype "power_in"))
      (node (ref "U4") (pin "7") (pinfunction "GND_7") (pintype "power_in"))
      (node (ref "U4") (pin "EPAD") (pinfunction "GND_EPAD") (pintype "power_in"))
      (node (ref "U5") (pin "1") (pinfunction "GND_1") (pintype "power_in"))
      (node (ref "U5") (pin "11") (pinfunction "GND_11") (pintype "power_in"))
      (node (ref "U5") (pin "12") (pinfunction "GND_12") (pintype "power_in"))
      (node (ref "U5") (pin "16") (pinfunction "GND_16") (pintype "power_in"))
      (node (ref "U5") (pin "6") (pinfunction "LBO_6") (pintype "open_collector"))
      (node (ref "U5") (pin "7") (pinfunction "LBI_7") (pintype "input"))
      (node (ref "U5") (pin "9") (pinfunction "GND_9") (pintype "power_in"))
      (node (ref "U5") (pin "PAD") (pinfunction "GND_PAD") (pintype "power_in"))
      (node (ref "U7") (pin "1") (pinfunction "GND_1") (pintype "input"))
      (node (ref "U8") (pin "2") (pinfunction "GND_2") (pintype "power_in"))
      (node (ref "U9") (pin "A6") (pinfunction "VSS_A6") (pintype "power_in"))
      (node (ref "U9") (pin "C4") (pinfunction "VSSQ_C4") (pintype "power_in"))
      (node (ref "U9") (pin "E7") (pinfunction "VSS_E7") (pintype "power_in"))
      (node (ref "U9") (pin "G5") (pinfunction "VSS_G5") (pintype "power_in"))
      (node (ref "U9") (pin "H10") (pinfunction "VSS_H10") (pintype "power_in"))
      (node (ref "U9") (pin "J5") (pinfunction "VSS_J5") (pintype "power_in"))
      (node (ref "U9") (pin "K8") (pinfunction "VSS_K8") (pintype "power_in"))
      (node (ref "U9") (pin "N2") (pinfunction "VSSQ_N2") (pintype "power_in"))
      (node (ref "U9") (pin "N5") (pinfunction "VSSQ_N5") (pintype "power_in"))
      (node (ref "U9") (pin "P4") (pinfunction "VSSQ_P4") (pintype "power_in"))
      (node (ref "U9") (pin "P6") (pinfunction "VSSQ_P6") (pintype "power_in"))
      (node (ref "X2") (pin "2") (pinfunction "SHIELD_2") (pintype "power_in"))
      (node (ref "X2") (pin "4") (pinfunction "SHIELD_4") (pintype "power_in"))
    )
    (net (code "16") (name "MAX4211-3V3") (class "Default")
      (node (ref "C5") (pin "1") (pinfunction "1_1") (pintype "passive"))
      (node (ref "U4") (pin "1") (pinfunction "VCC_1") (pintype "power_in"))
      (node (ref "U7") (pin "2") (pinfunction "OUT_2") (pintype "passive"))
    )
    (net (code "17") (name "N$2") (class "Default")
      (node (ref "R30") (pin "2") (pinfunction "2_2") (pintype "passive"))
      (node (ref "U4") (pin "9") (pinfunction "CIN2-_9") (pintype "input"))
    )
    (net (code "18") (name "NRESET") (class "Default")
      (node (ref "J7") (pin "10") (pinfunction "~{RESET}_10") (pintype "passive"))
      (node (ref "U$1") (pin "25") (pinfunction "NRST_25") (pintype "bidirectional"))
    )
    (net (code "19") (name "Net-(C2-Pad1)") (class "Default")
      (node (ref "C2") (pin "1") (pinfunction "1_1") (pintype "passive"))
      (node (ref "R36") (pin "2") (pinfunction "2_2") (pintype "passive"))
      (node (ref "R37") (pin "2") (pinfunction "2_2") (pintype "passive"))
    )
    (net (code "20") (name "Net-(CM1-CENTER)") (class "Default")
      (node (ref "CM1") (pin "RF") (pinfunction "CENTER_RF") (pintype "passive"))
      (node (ref "J2") (pin "FEED") (pinfunction "SIGNAL_FEED") (pintype "bidirectional"))
    )
    (net (code "21") (name "Net-(CM2-CENTER)") (class "Default")
      (node (ref "CM2") (pin "RF") (pinfunction "CENTER_RF") (pintype "passive"))
      (node (ref "J3") (pin "FEED") (pinfunction "SIGNAL_FEED") (pintype "bidirectional"))
    )
    (net (code "22") (name "Net-(CM3-CENTER)") (class "Default")
      (node (ref "CM3") (pin "RF") (pinfunction "CENTER_RF") (pintype "passive"))
      (node (ref "J4") (pin "FEED") (pinfunction "SIGNAL_FEED") (pintype "bidirectional"))
    )
    (net (code "23") (name "Net-(D1-PadA)") (class "Default")
      (node (ref "D1") (pin "A") (pinfunction "A_A") (pintype "passive"))
      (node (ref "R1") (pin "1") (pinfunction "1_1") (pintype "passive"))
    )
    (net (code "24") (name "Net-(D2-PadA)") (class "Default")
      (node (ref "D2") (pin "A") (pinfunction "A_A") (pintype "passive"))
      (node (ref "R2") (pin "1") (pinfunction "1_1") (pintype "passive"))
    )
    (net (code "25") (name "Net-(D3-PadA)") (class "Default")
      (node (ref "D3") (pin "A") (pinfunction "A_A") (pintype "passive"))
      (node (ref "R3") (pin "1") (pinfunction "1_1") (pintype "passive"))
    )
    (net (code "26") (name "Net-(L2-Pad1)") (class "Default")
      (node (ref "L2") (pin "1") (pinfunction "1_1") (pintype "passive"))
      (node (ref "U5") (pin "14") (pinfunction "SW_14") (pintype "output"))
      (node (ref "U5") (pin "15") (pinfunction "SW_15") (pintype "output"))
    )
    (net (code "27") (name "Net-(Q3-S)") (class "Default")
      (node (ref "C4") (pin "1") (pinfunction "1_1") (pintype "passive"))
      (node (ref "Q3") (pin "4") (pinfunction "S_4") (pintype "passive"))
      (node (ref "R29") (pin "2") (pinfunction "2_2") (pintype "passive"))
      (node (ref "R35") (pin "2") (pinfunction "2_2") (pintype "passive"))
      (node (ref "U4") (pin "15") (pinfunction "RS-_15") (pintype "passive"))
      (node (ref "U7") (pin "3") (pinfunction "IN_3") (pintype "input"))
    )
    (net (code "28") (name "Net-(U$1-BOOT0)") (class "Default")
      (node (ref "R4") (pin "2") (pinfunction "2_2") (pintype "passive"))
      (node (ref "U$1") (pin "138") (pinfunction "BOOT0_138") (pintype "bidirectional"))
    )
    (net (code "29") (name "Net-(U$1-PH0)") (class "Default")
      (node (ref "C30") (pin "1") (pinfunction "1_1") (pintype "passive"))
      (node (ref "U$1") (pin "23") (pinfunction "PH0_23") (pintype "bidirectional"))
      (node (ref "X2") (pin "3") (pinfunction "2_3") (pintype "passive"))
    )
    (net (code "30") (name "Net-(U$1-PH1)") (class "Default")
      (node (ref "C31") (pin "1") (pinfunction "1_1") (pintype "passive"))
      (node (ref "U$1") (pin "24") (pinfunction "PH1_24") (pintype "bidirectional"))
      (node (ref "X2") (pin "1") (pinfunction "1_1") (pintype "passive"))
    )
    (net (code "31") (name "Net-(U$1-VDDA)") (class "Default")
      (node (ref "E1") (pin "2") (pinfunction "2_2") (pintype "passive"))
      (node (ref "U$1") (pin "33") (pinfunction "VDDA_33") (pintype "bidirectional"))
    )
    (net (code "32") (name "Net-(U4-CIN1+)") (class "Default")
      (node (ref "R33") (pin "1") (pinfunction "1_1") (pintype "passive"))
      (node (ref "R34") (pin "2") (pinfunction "2_2") (pintype "passive"))
      (node (ref "TP11") (pin "1") (pinfunction "1_1") (pintype "passive"))
      (node (ref "U4") (pin "10") (pinfunction "CIN1+_10") (pintype "input"))
    )
    (net (code "33") (name "Net-(U4-CIN1-)") (class "Default")
      (node (ref "R31") (pin "1") (pinfunction "1_1") (pintype "passive"))
      (node (ref "R32") (pin "2") (pinfunction "2_2") (pintype "passive"))
      (node (ref "TP12") (pin "1") (pinfunction "1_1") (pintype "passive"))
      (node (ref "U4") (pin "11") (pinfunction "CIN1-_11") (pintype "input"))
    )
    (net (code "34") (name "Net-(U4-CIN2+)") (class "Default")
      (node (ref "R33") (pin "2") (pinfunction "2_2") (pintype "passive"))
      (node (ref "U4") (pin "12") (pinfunction "REF_12") (pintype "output"))
      (node (ref "U4") (pin "8") (pinfunction "CIN2+_8") (pintype "input"))
    )
    (net (code "35") (name "Net-(U4-INHIBIT)") (class "Default")
      (node (ref "R37") (pin "1") (pinfunction "1_1") (pintype "passive"))
      (node (ref "U4") (pin "5") (pinfunction "INHIBIT_5") (pintype "input"))
    )
    (net (code "36") (name "Net-(U4-IOUT)") (class "Default")
      (node (ref "R31") (pin "2") (pinfunction "2_2") (pintype "passive"))
      (node (ref "U4") (pin "14") (pinfunction "IOUT_14") (pintype "output"))
    )
    (net (code "37") (name "Net-(U4-POUT)") (class "Default")
      (node (ref "TP6") (pin "1") (pinfunction "1_1") (pintype "passive"))
      (node (ref "U4") (pin "13") (pinfunction "POUT_13") (pintype "output"))
    )
    (net (code "38") (name "Net-(U5-PG)") (class "Default")
      (node (ref "TP16") (pin "1") (pinfunction "1_1") (pintype "passive"))
      (node (ref "U5") (pin "13") (pinfunction "PG_13") (pintype "open_collector"))
    )
    (net (code "39") (name "Net-(U5-SYNC)") (class "Default")
      (node (ref "R10") (pin "2") (pinfunction "2_2") (pintype "passive"))
      (node (ref "R7") (pin "1") (pinfunction "1_1") (pintype "passive"))
      (node (ref "TP19") (pin "1") (pinfunction "1_1") (pintype "passive"))
      (node (ref "U5") (pin "5") (pinfunction "SYNC_5") (pintype "input"))
    )
    (net (code "40") (name "OPD_PWR") (class "Default")
      (node (ref "J6") (pin "15") (pinfunction "15_15") (pintype "passive"))
      (node (ref "J6") (pin "16") (pinfunction "16_16") (pintype "passive"))
    )
    (net (code "41") (name "OPD_SCL") (class "Default")
      (node (ref "J6") (pin "13") (pinfunction "13_13") (pintype "passive"))
      (node (ref "J6") (pin "14") (pinfunction "14_14") (pintype "passive"))
    )
    (net (code "42") (name "OPD_SDA") (class "Default")
      (node (ref "J6") (pin "11") (pinfunction "11_11") (pintype "passive"))
      (node (ref "J6") (pin "12") (pinfunction "12_12") (pintype "passive"))
    )
    (net (code "43") (name "PA0") (class "Default")
      (node (ref "R3") (pin "2") (pinfunction "2_2") (pintype "passive"))
      (node (ref "U$1") (pin "34") (pinfunction "PA0_34") (pintype "bidirectional"))
    )
    (net (code "44") (name "PA2{slash}USART2_TX") (class "Default")
      (node (ref "U$1") (pin "36") (pinfunction "PA2_36") (pintype "bidirectional"))
    )
    (net (code "45") (name "PA3{slash}USART2_RX") (class "Default")
      (node (ref "U$1") (pin "37") (pinfunction "PA3_37") (pintype "bidirectional"))
    )
    (net (code "46") (name "SPARE1") (class "Default")
      (node (ref "J6") (pin "10") (pinfunction "10_10") (pintype "passive"))
      (node (ref "J6") (pin "9") (pinfunction "9_9") (pintype "passive"))
    )
    (net (code "47") (name "SPARE2") (class "Default")
      (node (ref "J6") (pin "7") (pinfunction "7_7") (pintype "passive"))
      (node (ref "J6") (pin "8") (pinfunction "8_8") (pintype "passive"))
    )
    (net (code "48") (name "SPARE3") (class "Default")
      (node (ref "J6") (pin "5") (pinfunction "5_5") (pintype "passive"))
      (node (ref "J6") (pin "6") (pinfunction "6_6") (pintype "passive"))
    )
    (net (code "49") (name "SPARE4") (class "Default")
      (node (ref "J6") (pin "3") (pinfunction "3_3") (pintype "passive"))
      (node (ref "J6") (pin "4") (pinfunction "4_4") (pintype "passive"))
    )
    (net (code "50") (name "SPARE5") (class "Default")
      (node (ref "J6") (pin "1") (pinfunction "1_1") (pintype "passive"))
      (node (ref "J6") (pin "2") (pinfunction "2_2") (pintype "passive"))
    )
    (net (code "51") (name "SWCLK") (class "Default")
      (node (ref "J7") (pin "4") (pinfunction "SWDCLK/TCK_4") (pintype "passive"))
      (node (ref "U$1") (pin "109") (pinfunction "PA14_109") (pintype "bidirectional"))
    )
    (net (code "52") (name "SWDIO") (class "Default")
      (node (ref "J7") (pin "2") (pinfunction "SWDIO/TMS_2") (pintype "passive"))
      (node (ref "U$1") (pin "105") (pinfunction "PA13_105") (pintype "bidirectional"))
    )
    (net (code "53") (name "VBUS") (class "Default")
      (node (ref "J6") (pin "21") (pinfunction "21_21") (pintype "passive"))
      (node (ref "J6") (pin "22") (pinfunction "22_22") (pintype "passive"))
      (node (ref "J6") (pin "23") (pinfunction "23_23") (pintype "passive"))
      (node (ref "J6") (pin "24") (pinfunction "24_24") (pintype "passive"))
      (node (ref "J6") (pin "25") (pinfunction "25_25") (pintype "passive"))
      (node (ref "J6") (pin "26") (pinfunction "26_26") (pintype "passive"))
      (node (ref "R29") (pin "1") (pinfunction "1_1") (pintype "passive"))
      (node (ref "U4") (pin "16") (pinfunction "RS+_16") (pintype "passive"))
    )
    (net (code "54") (name "VBUSP") (class "Default")
      (node (ref "C10") (pin "1") (pinfunction "1_1") (pintype "passive"))
      (node (ref "C2") (pin "2") (pinfunction "2_2") (pintype "passive"))
      (node (ref "C7") (pin "1") (pinfunction "1_1") (pintype "passive"))
      (node (ref "Q3") (pin "1") (pinfunction "D_1") (pintype "passive"))
      (node (ref "Q3") (pin "2") (pinfunction "D_2") (pintype "passive"))
      (node (ref "Q3") (pin "5") (pinfunction "D_5") (pintype "passive"))
      (node (ref "Q3") (pin "6") (pinfunction "D_6") (pintype "passive"))
      (node (ref "R1") (pin "2") (pinfunction "2_2") (pintype "passive"))
      (node (ref "R7") (pin "2") (pinfunction "2_2") (pintype "passive"))
      (node (ref "TP9") (pin "1") (pinfunction "1_1") (pintype "passive"))
      (node (ref "U5") (pin "2") (pinfunction "VIN_2") (pintype "power_in"))
      (node (ref "U5") (pin "3") (pinfunction "VIN_3") (pintype "power_in"))
      (node (ref "U5") (pin "4") (pinfunction "EN_4") (pintype "input"))
      (node (ref "U5") (pin "8") (pinfunction "VIN_8") (pintype "power_in"))
    )
    (net (code "55") (name "VDDI") (class "Default")
      (node (ref "U9") (pin "C2") (pinfunction "VDDI_C2") (pintype "power_in"))
    )
    (net (code "56") (name "unconnected-(J7-NC{slash}TDI-Pad8)") (class "Default")
      (node (ref "J7") (pin "8") (pinfunction "NC/TDI_8") (pintype "passive"))
    )
    (net (code "57") (name "unconnected-(J7-SWO{slash}TDO-Pad6)") (class "Default")
      (node (ref "J7") (pin "6") (pinfunction "SWO/TDO_6") (pintype "passive"))
    )
    (net (code "58") (name "unconnected-(U$1-PA1-Pad35)") (class "Default")
      (node (ref "U$1") (pin "35") (pinfunction "PA1_35") (pintype "bidirectional"))
    )
    (net (code "59") (name "unconnected-(U$1-PA4-Pad40)") (class "Default")
      (node (ref "U$1") (pin "40") (pinfunction "PA4_40") (pintype "bidirectional"))
    )
    (net (code "60") (name "unconnected-(U$1-PA5-Pad41)") (class "Default")
      (node (ref "U$1") (pin "41") (pinfunction "PA5_41") (pintype "bidirectional"))
    )
    (net (code "61") (name "unconnected-(U$1-PA6-Pad42)") (class "Default")
      (node (ref "U$1") (pin "42") (pinfunction "PA6_42") (pintype "bidirectional"))
    )
    (net (code "62") (name "unconnected-(U$1-PA7-Pad43)") (class "Default")
      (node (ref "U$1") (pin "43") (pinfunction "PA7_43") (pintype "bidirectional"))
    )
    (net (code "63") (name "unconnected-(U$1-PA8-Pad100)") (class "Default")
      (node (ref "U$1") (pin "100") (pinfunction "PA8_100") (pintype "bidirectional"))
    )
    (net (code "64") (name "unconnected-(U$1-PA15-Pad110)") (class "Default")
      (node (ref "U$1") (pin "110") (pinfunction "PA15_110") (pintype "bidirectional"))
    )
    (net (code "65") (name "unconnected-(U$1-PB0-Pad46)") (class "Default")
      (node (ref "U$1") (pin "46") (pinfunction "PB0_46") (pintype "bidirectional"))
    )
    (net (code "66") (name "unconnected-(U$1-PB1-Pad47)") (class "Default")
      (node (ref "U$1") (pin "47") (pinfunction "PB1_47") (pintype "bidirectional"))
    )
    (net (code "67") (name "unconnected-(U$1-PB2-Pad48)") (class "Default")
      (node (ref "U$1") (pin "48") (pinfunction "PB2_48") (pintype "bidirectional"))
    )
    (net (code "68") (name "unconnected-(U$1-PB3-Pad133)") (class "Default")
      (node (ref "U$1") (pin "133") (pinfunction "PB3_133") (pintype "bidirectional"))
    )
    (net (code "69") (name "unconnected-(U$1-PB4-Pad134)") (class "Default")
      (node (ref "U$1") (pin "134") (pinfunction "PB4_134") (pintype "bidirectional"))
    )
    (net (code "70") (name "unconnected-(U$1-PB5-Pad135)") (class "Default")
      (node (ref "U$1") (pin "135") (pinfunction "PB5_135") (pintype "bidirectional"))
    )
    (net (code "71") (name "unconnected-(U$1-PB6-Pad136)") (class "Default")
      (node (ref "U$1") (pin "136") (pinfunction "PB6_136") (pintype "bidirectional"))
    )
    (net (code "72") (name "unconnected-(U$1-PB7-Pad137)") (class "Default")
      (node (ref "U$1") (pin "137") (pinfunction "PB7_137") (pintype "bidirectional"))
    )
    (net (code "73") (name "unconnected-(U$1-PB8-Pad139)") (class "Default")
      (node (ref "U$1") (pin "139") (pinfunction "PB8_139") (pintype "bidirectional"))
    )
    (net (code "74") (name "unconnected-(U$1-PB9-Pad140)") (class "Default")
      (node (ref "U$1") (pin "140") (pinfunction "PB9_140") (pintype "bidirectional"))
    )
    (net (code "75") (name "unconnected-(U$1-PB14-Pad75)") (class "Default")
      (node (ref "U$1") (pin "75") (pinfunction "PB14_75") (pintype "bidirectional"))
    )
    (net (code "76") (name "unconnected-(U$1-PB15-Pad76)") (class "Default")
      (node (ref "U$1") (pin "76") (pinfunction "PB15_76") (pintype "bidirectional"))
    )
    (net (code "77") (name "unconnected-(U$1-PC0-Pad26)") (class "Default")
      (node (ref "U$1") (pin "26") (pinfunction "PC0_26") (pintype "bidirectional"))
    )
    (net (code "78") (name "unconnected-(U$1-PC1-Pad27)") (class "Default")
      (node (ref "U$1") (pin "27") (pinfunction "PC1_27") (pintype "bidirectional"))
    )
    (net (code "79") (name "unconnected-(U$1-PC2-Pad28)") (class "Default")
      (node (ref "U$1") (pin "28") (pinfunction "PC2_28") (pintype "bidirectional"))
    )
    (net (code "80") (name "unconnected-(U$1-PC3-Pad29)") (class "Default")
      (node (ref "U$1") (pin "29") (pinfunction "PC3_29") (pintype "bidirectional"))
    )
    (net (code "81") (name "unconnected-(U$1-PC4-Pad44)") (class "Default")
      (node (ref "U$1") (pin "44") (pinfunction "PC4_44") (pintype "bidirectional"))
    )
    (net (code "82") (name "unconnected-(U$1-PC5-Pad45)") (class "Default")
      (node (ref "U$1") (pin "45") (pinfunction "PC5_45") (pintype "bidirectional"))
    )
    (net (code "83") (name "unconnected-(U$1-PC6-Pad96)") (class "Default")
      (node (ref "U$1") (pin "96") (pinfunction "PC6_96") (pintype "bidirectional"))
    )
    (net (code "84") (name "unconnected-(U$1-PC7-Pad97)") (class "Default")
      (node (ref "U$1") (pin "97") (pinfunction "PC7_97") (pintype "bidirectional"))
    )
    (net (code "85") (name "unconnected-(U$1-PC8-Pad98)") (class "Default")
      (node (ref "U$1") (pin "98") (pinfunction "PC8_98") (pintype "bidirectional"))
    )
    (net (code "86") (name "unconnected-(U$1-PC9-Pad99)") (class "Default")
      (node (ref "U$1") (pin "99") (pinfunction "PC9_99") (pintype "bidirectional"))
    )
    (net (code "87") (name "unconnected-(U$1-PC10-Pad111)") (class "Default")
      (node (ref "U$1") (pin "111") (pinfunction "PC10_111") (pintype "bidirectional"))
    )
    (net (code "88") (name "unconnected-(U$1-PC11-Pad112)") (class "Default")
      (node (ref "U$1") (pin "112") (pinfunction "PC11_112") (pintype "bidirectional"))
    )
    (net (code "89") (name "unconnected-(U$1-PC12-Pad113)") (class "Default")
      (node (ref "U$1") (pin "113") (pinfunction "PC12_113") (pintype "bidirectional"))
    )
    (net (code "90") (name "unconnected-(U$1-PC13-Pad7)") (class "Default")
      (node (ref "U$1") (pin "7") (pinfunction "PC13_7") (pintype "bidirectional"))
    )
    (net (code "91") (name "unconnected-(U$1-PC14-Pad8)") (class "Default")
      (node (ref "U$1") (pin "8") (pinfunction "PC14_8") (pintype "bidirectional"))
    )
    (net (code "92") (name "unconnected-(U$1-PC15-Pad9)") (class "Default")
      (node (ref "U$1") (pin "9") (pinfunction "PC15_9") (pintype "bidirectional"))
    )
    (net (code "93") (name "unconnected-(U$1-PD0-Pad114)") (class "Default")
      (node (ref "U$1") (pin "114") (pinfunction "PD0_114") (pintype "bidirectional"))
    )
    (net (code "94") (name "unconnected-(U$1-PD1-Pad115)") (class "Default")
      (node (ref "U$1") (pin "115") (pinfunction "PD1_115") (pintype "bidirectional"))
    )
    (net (code "95") (name "unconnected-(U$1-PD2-Pad116)") (class "Default")
      (node (ref "U$1") (pin "116") (pinfunction "PD2_116") (pintype "bidirectional"))
    )
    (net (code "96") (name "unconnected-(U$1-PD3-Pad117)") (class "Default")
      (node (ref "U$1") (pin "117") (pinfunction "PD3_117") (pintype "bidirectional"))
    )
    (net (code "97") (name "unconnected-(U$1-PD4-Pad118)") (class "Default")
      (node (ref "U$1") (pin "118") (pinfunction "PD4_118") (pintype "bidirectional"))
    )
    (net (code "98") (name "unconnected-(U$1-PD5-Pad119)") (class "Default")
      (node (ref "U$1") (pin "119") (pinfunction "PD5_119") (pintype "bidirectional"))
    )
    (net (code "99") (name "unconnected-(U$1-PD6-Pad122)") (class "Default")
      (node (ref "U$1") (pin "122") (pinfunction "PD6_122") (pintype "bidirectional"))
    )
    (net (code "100") (name "unconnected-(U$1-PD7-Pad123)") (class "Default")
      (node (ref "U$1") (pin "123") (pinfunction "PD7_123") (pintype "bidirectional"))
    )
    (net (code "101") (name "unconnected-(U$1-PD8-Pad77)") (class "Default")
      (node (ref "U$1") (pin "77") (pinfunction "PD8_77") (pintype "bidirectional"))
    )
    (net (code "102") (name "unconnected-(U$1-PD9-Pad78)") (class "Default")
      (node (ref "U$1") (pin "78") (pinfunction "PD9_78") (pintype "bidirectional"))
    )
    (net (code "103") (name "unconnected-(U$1-PD10-Pad79)") (class "Default")
      (node (ref "U$1") (pin "79") (pinfunction "PD10_79") (pintype "bidirectional"))
    )
    (net (code "104") (name "unconnected-(U$1-PD11-Pad80)") (class "Default")
      (node (ref "U$1") (pin "80") (pinfunction "PD11_80") (pintype "bidirectional"))
    )
    (net (code "105") (name "unconnected-(U$1-PD12-Pad81)") (class "Default")
      (node (ref "U$1") (pin "81") (pinfunction "PD12_81") (pintype "bidirectional"))
    )
    (net (code "106") (name "unconnected-(U$1-PD13-Pad82)") (class "Default")
      (node (ref "U$1") (pin "82") (pinfunction "PD13_82") (pintype "bidirectional"))
    )
    (net (code "107") (name "unconnected-(U$1-PD14-Pad85)") (class "Default")
      (node (ref "U$1") (pin "85") (pinfunction "PD14_85") (pintype "bidirectional"))
    )
    (net (code "108") (name "unconnected-(U$1-PD15-Pad86)") (class "Default")
      (node (ref "U$1") (pin "86") (pinfunction "PD15_86") (pintype "bidirectional"))
    )
    (net (code "109") (name "unconnected-(U$1-PDR_ON-Pad143)") (class "Default")
      (node (ref "U$1") (pin "143") (pinfunction "PDR_ON_143") (pintype "bidirectional"))
    )
    (net (code "110") (name "unconnected-(U$1-PE0-Pad141)") (class "Default")
      (node (ref "U$1") (pin "141") (pinfunction "PE0_141") (pintype "bidirectional"))
    )
    (net (code "111") (name "unconnected-(U$1-PE1-Pad142)") (class "Default")
      (node (ref "U$1") (pin "142") (pinfunction "PE1_142") (pintype "bidirectional"))
    )
    (net (code "112") (name "unconnected-(U$1-PE2-Pad1)") (class "Default")
      (node (ref "U$1") (pin "1") (pinfunction "PE2_1") (pintype "bidirectional"))
    )
    (net (code "113") (name "unconnected-(U$1-PE3-Pad2)") (class "Default")
      (node (ref "U$1") (pin "2") (pinfunction "PE3_2") (pintype "bidirectional"))
    )
    (net (code "114") (name "unconnected-(U$1-PE4-Pad3)") (class "Default")
      (node (ref "U$1") (pin "3") (pinfunction "PE4_3") (pintype "bidirectional"))
    )
    (net (code "115") (name "unconnected-(U$1-PE5-Pad4)") (class "Default")
      (node (ref "U$1") (pin "4") (pinfunction "PE5_4") (pintype "bidirectional"))
    )
    (net (code "116") (name "unconnected-(U$1-PE6-Pad5)") (class "Default")
      (node (ref "U$1") (pin "5") (pinfunction "PE6_5") (pintype "bidirectional"))
    )
    (net (code "117") (name "unconnected-(U$1-PE7-Pad58)") (class "Default")
      (node (ref "U$1") (pin "58") (pinfunction "PE7_58") (pintype "bidirectional"))
    )
    (net (code "118") (name "unconnected-(U$1-PE8-Pad59)") (class "Default")
      (node (ref "U$1") (pin "59") (pinfunction "PE8_59") (pintype "bidirectional"))
    )
    (net (code "119") (name "unconnected-(U$1-PE9-Pad60)") (class "Default")
      (node (ref "U$1") (pin "60") (pinfunction "PE9_60") (pintype "bidirectional"))
    )
    (net (code "120") (name "unconnected-(U$1-PE10-Pad63)") (class "Default")
      (node (ref "U$1") (pin "63") (pinfunction "PE10_63") (pintype "bidirectional"))
    )
    (net (code "121") (name "unconnected-(U$1-PE11-Pad64)") (class "Default")
      (node (ref "U$1") (pin "64") (pinfunction "PE11_64") (pintype "bidirectional"))
    )
    (net (code "122") (name "unconnected-(U$1-PE12-Pad65)") (class "Default")
      (node (ref "U$1") (pin "65") (pinfunction "PE12_65") (pintype "bidirectional"))
    )
    (net (code "123") (name "unconnected-(U$1-PE13-Pad66)") (class "Default")
      (node (ref "U$1") (pin "66") (pinfunction "PE13_66") (pintype "bidirectional"))
    )
    (net (code "124") (name "unconnected-(U$1-PE14-Pad67)") (class "Default")
      (node (ref "U$1") (pin "67") (pinfunction "PE14_67") (pintype "bidirectional"))
    )
    (net (code "125") (name "unconnected-(U$1-PE15-Pad68)") (class "Default")
      (node (ref "U$1") (pin "68") (pinfunction "PE15_68") (pintype "bidirectional"))
    )
    (net (code "126") (name "unconnected-(U$1-PF0-Pad10)") (class "Default")
      (node (ref "U$1") (pin "10") (pinfunction "PF0_10") (pintype "bidirectional"))
    )
    (net (code "127") (name "unconnected-(U$1-PF1-Pad11)") (class "Default")
      (node (ref "U$1") (pin "11") (pinfunction "PF1_11") (pintype "bidirectional"))
    )
    (net (code "128") (name "unconnected-(U$1-PF2-Pad12)") (class "Default")
      (node (ref "U$1") (pin "12") (pinfunction "PF2_12") (pintype "bidirectional"))
    )
    (net (code "129") (name "unconnected-(U$1-PF3-Pad13)") (class "Default")
      (node (ref "U$1") (pin "13") (pinfunction "PF3_13") (pintype "bidirectional"))
    )
    (net (code "130") (name "unconnected-(U$1-PF4-Pad14)") (class "Default")
      (node (ref "U$1") (pin "14") (pinfunction "PF4_14") (pintype "bidirectional"))
    )
    (net (code "131") (name "unconnected-(U$1-PF5-Pad15)") (class "Default")
      (node (ref "U$1") (pin "15") (pinfunction "PF5_15") (pintype "bidirectional"))
    )
    (net (code "132") (name "unconnected-(U$1-PF6-Pad18)") (class "Default")
      (node (ref "U$1") (pin "18") (pinfunction "PF6_18") (pintype "bidirectional"))
    )
    (net (code "133") (name "unconnected-(U$1-PF7-Pad19)") (class "Default")
      (node (ref "U$1") (pin "19") (pinfunction "PF7_19") (pintype "bidirectional"))
    )
    (net (code "134") (name "unconnected-(U$1-PF8-Pad20)") (class "Default")
      (node (ref "U$1") (pin "20") (pinfunction "PF8_20") (pintype "bidirectional"))
    )
    (net (code "135") (name "unconnected-(U$1-PF9-Pad21)") (class "Default")
      (node (ref "U$1") (pin "21") (pinfunction "PF9_21") (pintype "bidirectional"))
    )
    (net (code "136") (name "unconnected-(U$1-PF10-Pad22)") (class "Default")
      (node (ref "U$1") (pin "22") (pinfunction "PF10_22") (pintype "bidirectional"))
    )
    (net (code "137") (name "unconnected-(U$1-PF11-Pad49)") (class "Default")
      (node (ref "U$1") (pin "49") (pinfunction "PF11_49") (pintype "bidirectional"))
    )
    (net (code "138") (name "unconnected-(U$1-PF12-Pad50)") (class "Default")
      (node (ref "U$1") (pin "50") (pinfunction "PF12_50") (pintype "bidirectional"))
    )
    (net (code "139") (name "unconnected-(U$1-PF13-Pad53)") (class "Default")
      (node (ref "U$1") (pin "53") (pinfunction "PF13_53") (pintype "bidirectional"))
    )
    (net (code "140") (name "unconnected-(U$1-PF14-Pad54)") (class "Default")
      (node (ref "U$1") (pin "54") (pinfunction "PF14_54") (pintype "bidirectional"))
    )
    (net (code "141") (name "unconnected-(U$1-PF15-Pad55)") (class "Default")
      (node (ref "U$1") (pin "55") (pinfunction "PF15_55") (pintype "bidirectional"))
    )
    (net (code "142") (name "unconnected-(U$1-PG0-Pad56)") (class "Default")
      (node (ref "U$1") (pin "56") (pinfunction "PG0_56") (pintype "bidirectional"))
    )
    (net (code "143") (name "unconnected-(U$1-PG1-Pad57)") (class "Default")
      (node (ref "U$1") (pin "57") (pinfunction "PG1_57") (pintype "bidirectional"))
    )
    (net (code "144") (name "unconnected-(U$1-PG2-Pad87)") (class "Default")
      (node (ref "U$1") (pin "87") (pinfunction "PG2_87") (pintype "bidirectional"))
    )
    (net (code "145") (name "unconnected-(U$1-PG3-Pad88)") (class "Default")
      (node (ref "U$1") (pin "88") (pinfunction "PG3_88") (pintype "bidirectional"))
    )
    (net (code "146") (name "unconnected-(U$1-PG4-Pad89)") (class "Default")
      (node (ref "U$1") (pin "89") (pinfunction "PG4_89") (pintype "bidirectional"))
    )
    (net (code "147") (name "unconnected-(U$1-PG5-Pad90)") (class "Default")
      (node (ref "U$1") (pin "90") (pinfunction "PG5_90") (pintype "bidirectional"))
    )
    (net (code "148") (name "unconnected-(U$1-PG6-Pad91)") (class "Default")
      (node (ref "U$1") (pin "91") (pinfunction "PG6_91") (pintype "bidirectional"))
    )
    (net (code "149") (name "unconnected-(U$1-PG7-Pad92)") (class "Default")
      (node (ref "U$1") (pin "92") (pinfunction "PG7_92") (pintype "bidirectional"))
    )
    (net (code "150") (name "unconnected-(U$1-PG8-Pad93)") (class "Default")
      (node (ref "U$1") (pin "93") (pinfunction "PG8_93") (pintype "bidirectional"))
    )
    (net (code "151") (name "unconnected-(U$1-PG9-Pad124)") (class "Default")
      (node (ref "U$1") (pin "124") (pinfunction "PG9_124") (pintype "bidirectional"))
    )
    (net (code "152") (name "unconnected-(U$1-PG10-Pad125)") (class "Default")
      (node (ref "U$1") (pin "125") (pinfunction "PG10_125") (pintype "bidirectional"))
    )
    (net (code "153") (name "unconnected-(U$1-PG11-Pad126)") (class "Default")
      (node (ref "U$1") (pin "126") (pinfunction "PG11_126") (pintype "bidirectional"))
    )
    (net (code "154") (name "unconnected-(U$1-PG12-Pad127)") (class "Default")
      (node (ref "U$1") (pin "127") (pinfunction "PG12_127") (pintype "bidirectional"))
    )
    (net (code "155") (name "unconnected-(U$1-PG13-Pad128)") (class "Default")
      (node (ref "U$1") (pin "128") (pinfunction "PG13_128") (pintype "bidirectional"))
    )
    (net (code "156") (name "unconnected-(U$1-PG14-Pad129)") (class "Default")
      (node (ref "U$1") (pin "129") (pinfunction "PG14_129") (pintype "bidirectional"))
    )
    (net (code "157") (name "unconnected-(U$1-PG15-Pad132)") (class "Default")
      (node (ref "U$1") (pin "132") (pinfunction "PG15_132") (pintype "bidirectional"))
    )
    (net (code "158") (name "unconnected-(U$1-VCAP_1-Pad71)") (class "Default")
      (node (ref "U$1") (pin "71") (pinfunction "VCAP_1_71") (pintype "bidirectional"))
    )
    (net (code "159") (name "unconnected-(U$1-VCAP_2-Pad106)") (class "Default")
      (node (ref "U$1") (pin "106") (pinfunction "VCAP_2_106") (pintype "bidirectional"))
    )
    (net (code "160") (name "unconnected-(U$1-VDDUSB-Pad95)") (class "Default")
      (node (ref "U$1") (pin "95") (pinfunction "VDDUSB_95") (pintype "bidirectional"))
    )
    (net (code "161") (name "unconnected-(U$1-VREF+-Pad32)") (class "Default")
      (node (ref "U$1") (pin "32") (pinfunction "VREF+_32") (pintype "bidirectional"))
    )
    (net (code "162") (name "unconnected-(U9-CLK-PadM6)") (class "Default")
      (node (ref "U9") (pin "M6") (pinfunction "CLK_M6") (pintype "input"))
    )
    (net (code "163") (name "unconnected-(U9-CMD-PadM5)") (class "Default")
      (node (ref "U9") (pin "M5") (pinfunction "CMD_M5") (pintype "input"))
    )
    (net (code "164") (name "unconnected-(U9-DAT0-PadA3)") (class "Default")
      (node (ref "U9") (pin "A3") (pinfunction "DAT0_A3") (pintype "bidirectional"))
    )
    (net (code "165") (name "unconnected-(U9-DAT1-PadA4)") (class "Default")
      (node (ref "U9") (pin "A4") (pinfunction "DAT1_A4") (pintype "bidirectional"))
    )
    (net (code "166") (name "unconnected-(U9-DAT2-PadA5)") (class "Default")
      (node (ref "U9") (pin "A5") (pinfunction "DAT2_A5") (pintype "bidirectional"))
    )
    (net (code "167") (name "unconnected-(U9-DAT3-PadB2)") (class "Default")
      (node (ref "U9") (pin "B2") (pinfunction "DAT3_B2") (pintype "bidirectional"))
    )
    (net (code "168") (name "unconnected-(U9-DAT4-PadB3)") (class "Default")
      (node (ref "U9") (pin "B3") (pinfunction "DAT4_B3") (pintype "bidirectional"))
    )
    (net (code "169") (name "unconnected-(U9-DAT5-PadB4)") (class "Default")
      (node (ref "U9") (pin "B4") (pinfunction "DAT5_B4") (pintype "bidirectional"))
    )
    (net (code "170") (name "unconnected-(U9-DAT6-PadB5)") (class "Default")
      (node (ref "U9") (pin "B5") (pinfunction "DAT6_B5") (pintype "bidirectional"))
    )
    (net (code "171") (name "unconnected-(U9-DAT7-PadB6)") (class "Default")
      (node (ref "U9") (pin "B6") (pinfunction "DAT7_B6") (pintype "bidirectional"))
    )
    (net (code "172") (name "unconnected-(U9-DS-PadH5)") (class "Default")
      (node (ref "U9") (pin "H5") (pinfunction "DS_H5") (pintype "output"))
    )
    (net (code "173") (name "unconnected-(U9-RST_N-PadK5)") (class "Default")
      (node (ref "U9") (pin "K5") (pinfunction "RST_N_K5") (pintype "input"))
    )
    (net (code "174") (name "~{SD}") (class "Default")
      (node (ref "J6") (pin "39") (pinfunction "39_39") (pintype "passive"))
      (node (ref "J6") (pin "40") (pinfunction "40_40") (pintype "passive"))
    )
  )
)
